# MAX17320.net
KiCad netlist of a schematic drawn in Altium Designer
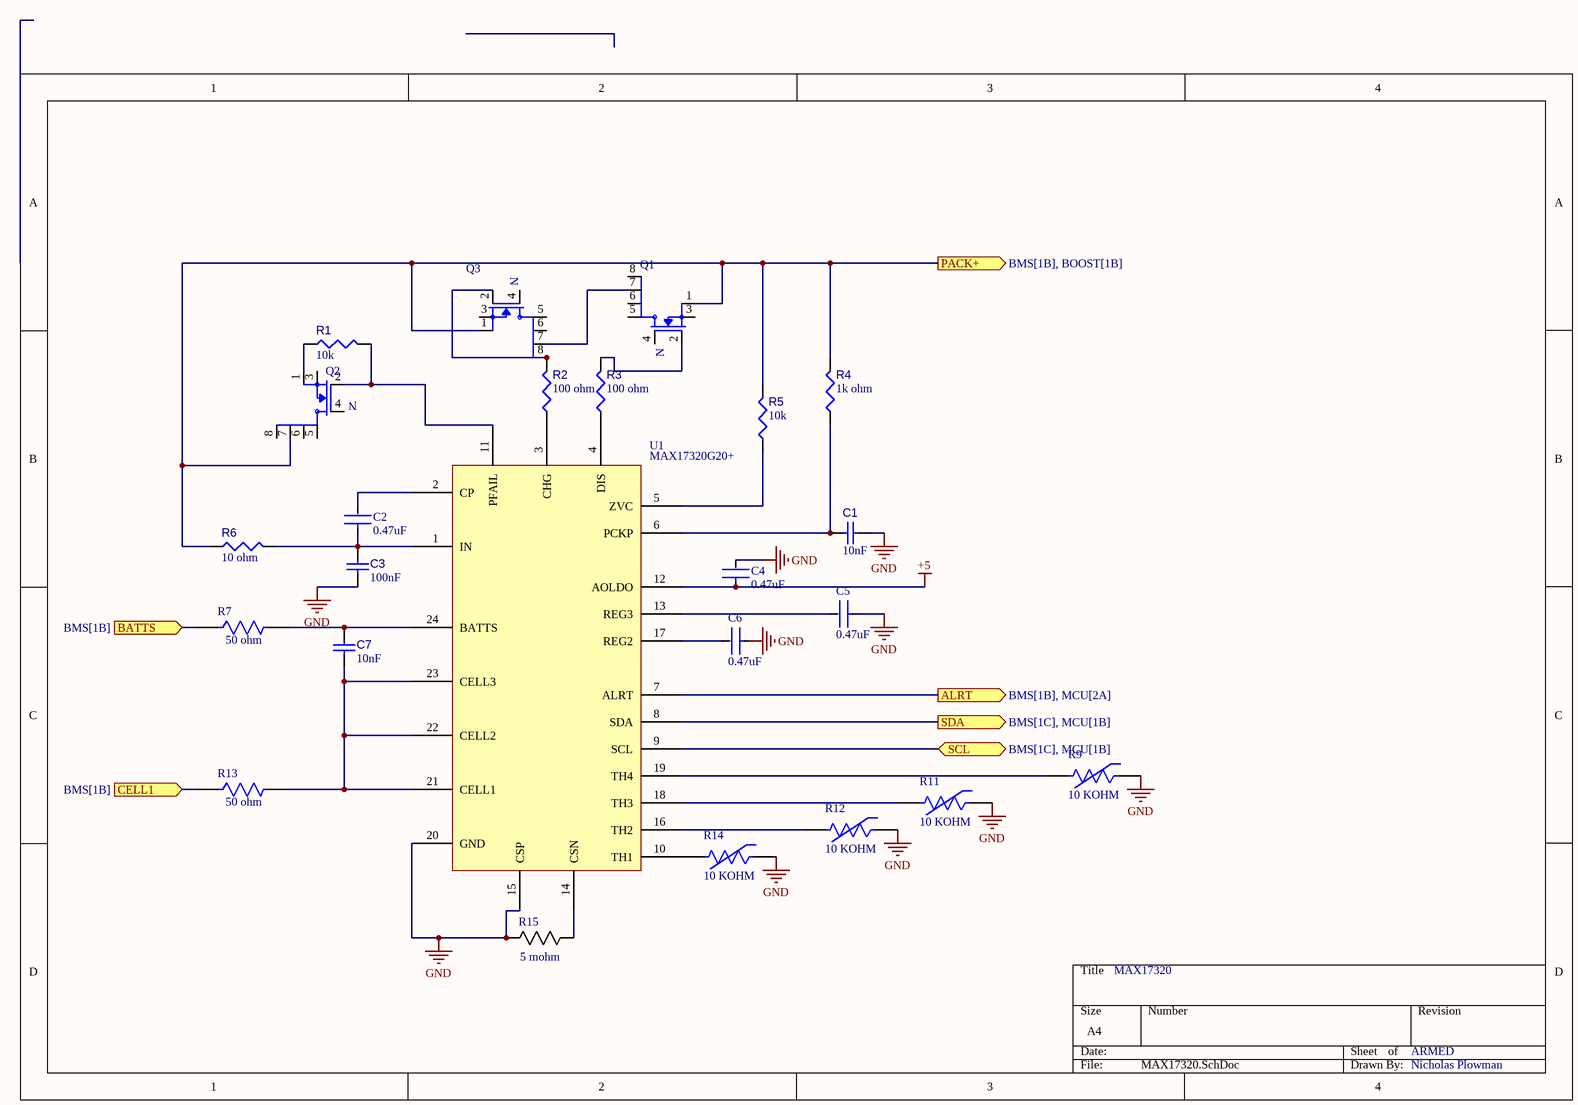
[diagram p0: MAX17320.SchDoc]

(export (version "E")
  (design (tool "Eeschema 10.0.6"))
  (components
    (comp (ref "C1")
      (value "10nF")
      (footprint "CAPC0402(1005)60_L")
      (description "Chip Capacitor, 10nF +/-20%, 50V, 0402, Thickness 0.6 mm")
      (fields (field (name "TOLERANCE") "5%") (field (name "Comment") "Capacitor 10nF +/-20% 50V 0402"))
      (libsource (lib "Americas- Augmented Reality for Medicine- University of Calgary") (part "CAP-NP-2"))
    )
    (comp (ref "C2")
      (value "0.47uF")
      (footprint "FP-GRM15-0_1-MFG")
      (description "Multilayer Ceramic Capacitor, 0.47 uF, 10 V, ± 10%, X5R, 0402 [1005 Metric]")
      (fields (field (name "Comment") "GRM155R61A474KE15D"))
      (libsource (lib "Americas- Augmented Reality for Medicine- University of Calgary") (part "11868f565c42a9108669ba33697ecf6"))
    )
    (comp (ref "C3")
      (value "100nF")
      (footprint "CAPC1005X56X25LL10T15")
      (description "Chip Capacitor, 0.1 uF, +/- 5%, 16 V, 0402 (1005 Metric)")
      (fields (field (name "TOLERANCE") "5%") (field (name "Comment") "Capacitor 0.1 uF +/- 5% 16 V 0402"))
      (libsource (lib "Americas- Augmented Reality for Medicine- University of Calgary") (part "CAP-NP-2"))
    )
    (comp (ref "C4")
      (value "0.47uF")
      (footprint "FP-GRM15-0_1-MFG")
      (description "Multilayer Ceramic Capacitor, 0.47 uF, 10 V, ± 10%, X5R, 0402 [1005 Metric]")
      (fields (field (name "Comment") "GRM155R61A474KE15D"))
      (libsource (lib "Americas- Augmented Reality for Medicine- University of Calgary") (part "11868f565c42a9108669ba33697ecf6"))
    )
    (comp (ref "C5")
      (value "0.47uF")
      (footprint "FP-GRM15-0_1-MFG")
      (description "Multilayer Ceramic Capacitor, 0.47 uF, 10 V, ± 10%, X5R, 0402 [1005 Metric]")
      (fields (field (name "Comment") "GRM155R61A474KE15D"))
      (libsource (lib "Americas- Augmented Reality for Medicine- University of Calgary") (part "11868f565c42a9108669ba33697ecf6"))
    )
    (comp (ref "C6")
      (value "0.47uF")
      (footprint "FP-GRM15-0_1-MFG")
      (description "Multilayer Ceramic Capacitor, 0.47 uF, 10 V, ± 10%, X5R, 0402 [1005 Metric]")
      (fields (field (name "Comment") "GRM155R61A474KE15D"))
      (libsource (lib "Americas- Augmented Reality for Medicine- University of Calgary") (part "11868f565c42a9108669ba33697ecf6"))
    )
    (comp (ref "C7")
      (value "10nF")
      (footprint "CAPC0402(1005)60_L")
      (description "Chip Capacitor, 10nF +/-20%, 50V, 0402, Thickness 0.6 mm")
      (fields (field (name "TOLERANCE") "5%") (field (name "Comment") "Capacitor 10nF +/-20% 50V 0402"))
      (libsource (lib "Americas- Augmented Reality for Medicine- University of Calgary") (part "CAP-NP-2"))
    )
    (comp (ref "Q1")
      (value "DN2625DK6-G-ND")
      (footprint "DN2625DK6-G-ND-Footprint-1")
      (description "MOSFET 2N-CH 250V 1.1A 8DFN")
      (libsource (lib "Americas- Augmented Reality for Medicine- University of Calgary") (part "DN2625DK6-G-ND-Symbol-1"))
    )
    (comp (ref "Q2")
      (value "DN2625DK6-G-ND")
      (footprint "DN2625DK6-G-ND-Footprint-1")
      (description "MOSFET 2N-CH 250V 1.1A 8DFN")
      (libsource (lib "Americas- Augmented Reality for Medicine- University of Calgary") (part "DN2625DK6-G-ND-Symbol-1"))
    )
    (comp (ref "Q3")
      (value "DN2625DK6-G-ND")
      (footprint "DN2625DK6-G-ND-Footprint-1")
      (description "MOSFET 2N-CH 250V 1.1A 8DFN")
      (libsource (lib "Americas- Augmented Reality for Medicine- University of Calgary") (part "DN2625DK6-G-ND-Symbol-1"))
    )
    (comp (ref "R1")
      (value "10k")
      (footprint "RESC1005X40X25ML05T05")
      (description "Chip Resistor, 10 KOhm, +/- 1%, 0.1 W, -55 to 155 degC, 0402 (1005 Metric)")
      (fields (field (name "TOLERANCE") "1%") (field (name "POWER") "100mW"))
      (libsource (lib "Americas- Augmented Reality for Medicine- University of Calgary") (part "RES-2"))
    )
    (comp (ref "R2")
      (value "100 ohm")
      (footprint "RESC0402(1005)_L")
      (description "100R 0.063W 1% 0402 (1005 Metric)  SMD")
      (fields (field (name "TOLERANCE") "1%") (field (name "POWER") "63mW"))
      (libsource (lib "Americas- Augmented Reality for Medicine- University of Calgary") (part "100R2F"))
    )
    (comp (ref "R3")
      (value "100 ohm")
      (footprint "RESC0402(1005)_L")
      (description "100R 0.063W 1% 0402 (1005 Metric)  SMD")
      (fields (field (name "TOLERANCE") "1%") (field (name "POWER") "63mW"))
      (libsource (lib "Americas- Augmented Reality for Medicine- University of Calgary") (part "100R2F"))
    )
    (comp (ref "R4")
      (value "1k ohm")
      (footprint "RESC0402(1005)_L")
      (description "1K 0.063W 5% 0402 (1005 Metric)  SMD")
      (fields (field (name "POWER") "63mW") (field (name "TOLERANCE") "5%"))
      (libsource (lib "Americas- Augmented Reality for Medicine- University of Calgary") (part "1KR2J"))
    )
    (comp (ref "R5")
      (value "10k")
      (footprint "RESC1005X40X25ML05T05")
      (description "Chip Resistor, 10 KOhm, +/- 1%, 0.1 W, -55 to 155 degC, 0402 (1005 Metric)")
      (fields (field (name "TOLERANCE") "1%") (field (name "POWER") "100mW"))
      (libsource (lib "Americas- Augmented Reality for Medicine- University of Calgary") (part "RES-2"))
    )
    (comp (ref "R6")
      (value "10 ohm")
      (footprint "RESC0402(1005)_L")
      (description "10R 0.063W 1% 0402 (1005 Metric)  SMD")
      (fields (field (name "TOLERANCE") "1%") (field (name "POWER") "63mW"))
      (libsource (lib "Americas- Augmented Reality for Medicine- University of Calgary") (part "10R2F"))
    )
    (comp (ref "R7")
      (value "50 ohm")
      (footprint "FP-CRCW0603-e3-IPC_A")
      (description "SMD Chip Resistor, 50 Ohm, ± 1%, 100 mW, 0603 [1608 Metric], Thick Film, General Purpose")
      (fields (field (name "Comment") "CRCW060350R0FKEA"))
      (libsource (lib "Americas- Augmented Reality for Medicine- University of Calgary") (part "1029c3af85768c4190bb7ad29bc67b5"))
    )
    (comp (ref "R9")
      (value "10 KOHM")
      (footprint "FP-NCP15-NCU15-0_05-MFG")
      (description "Ntc Thermistor, Aec-Q200, 10Kohm, 0402 Rohs Compliant: Yes")
      (fields (field (name "TOLERANCE") "1%"))
      (libsource (lib "Americas- Augmented Reality for Medicine- University of Calgary") (part "3b148a6ebabc5fb4d708a66c052d352"))
    )
    (comp (ref "R11")
      (value "10 KOHM")
      (footprint "FP-NCP15-NCU15-0_05-MFG")
      (description "Ntc Thermistor, Aec-Q200, 10Kohm, 0402 Rohs Compliant: Yes")
      (fields (field (name "TOLERANCE") "1%"))
      (libsource (lib "Americas- Augmented Reality for Medicine- University of Calgary") (part "3b148a6ebabc5fb4d708a66c052d352"))
    )
    (comp (ref "R12")
      (value "10 KOHM")
      (footprint "FP-NCP15-NCU15-0_05-MFG")
      (description "Ntc Thermistor, Aec-Q200, 10Kohm, 0402 Rohs Compliant: Yes")
      (fields (field (name "TOLERANCE") "1%"))
      (libsource (lib "Americas- Augmented Reality for Medicine- University of Calgary") (part "3b148a6ebabc5fb4d708a66c052d352"))
    )
    (comp (ref "R13")
      (value "50 ohm")
      (footprint "FP-CRCW0603-e3-IPC_A")
      (description "SMD Chip Resistor, 50 Ohm, ± 1%, 100 mW, 0603 [1608 Metric], Thick Film, General Purpose")
      (fields (field (name "Comment") "CRCW060350R0FKEA"))
      (libsource (lib "Americas- Augmented Reality for Medicine- University of Calgary") (part "1029c3af85768c4190bb7ad29bc67b5"))
    )
    (comp (ref "R14")
      (value "10 KOHM")
      (footprint "FP-NCP15-NCU15-0_05-MFG")
      (description "Ntc Thermistor, Aec-Q200, 10Kohm, 0402 Rohs Compliant: Yes")
      (fields (field (name "TOLERANCE") "1%"))
      (libsource (lib "Americas- Augmented Reality for Medicine- University of Calgary") (part "3b148a6ebabc5fb4d708a66c052d352"))
    )
    (comp (ref "R15")
      (value "PA2512FKF7W0R005E")
      (footprint "PA2512FKF7W0R005E-Footprint-1")
      (description "Res Thin Film 2512 5m Ohm 1% 2W ±100ppm/°C Molded SMD Embossed T/R")
      (fields (field (name "PARAMETER 1") "5 mohm"))
      (libsource (lib "Americas- Augmented Reality for Medicine- University of Calgary") (part "PA2512FKF7W0R005E-Symbol-1"))
    )
    (comp (ref "U1")
      (value "MAX17320G20+")
      (footprint "MAX17320G12+-Footprint-1")
      (description "Fuel Gauge 2S-4S ModelGauge m5 EZ with Protector I2C 4.2V to 18V 24-Pin TQFN")
      (libsource (lib "Americas- Augmented Reality for Medicine- University of Calgary") (part "MAX17320G12+-Symbol-1"))
    )
  )
  (nets
    (net (code "1") (name "+5") (class "Default")
      (node (ref "C4") (pin "1") (pinfunction "1_1") (pintype "passive"))
      (node (ref "U1") (pin "12") (pinfunction "AOLDO_12") (pintype "passive"))
    )
    (net (code "2") (name "/ALRT") (class "Default")
      (node (ref "U1") (pin "7") (pinfunction "ALRT_7") (pintype "passive"))
    )
    (net (code "3") (name "/BATTS") (class "Default")
      (node (ref "R7") (pin "1") (pinfunction "1_1") (pintype "passive"))
    )
    (net (code "4") (name "/CELL1") (class "Default")
      (node (ref "R13") (pin "1") (pinfunction "1_1") (pintype "passive"))
    )
    (net (code "5") (name "/PACK+") (class "Default")
      (node (ref "Q1") (pin "1") (pinfunction "S1_1") (pintype "passive"))
      (node (ref "Q2") (pin "7") (pinfunction "D1_1_7") (pintype "passive"))
      (node (ref "Q3") (pin "1") (pinfunction "S1_1") (pintype "passive"))
      (node (ref "R4") (pin "2") (pinfunction "2_2") (pintype "passive"))
      (node (ref "R5") (pin "2") (pinfunction "2_2") (pintype "passive"))
      (node (ref "R6") (pin "1") (pinfunction "1_1") (pintype "passive"))
    )
    (net (code "6") (name "/SCL") (class "Default")
      (node (ref "U1") (pin "9") (pinfunction "SCL_9") (pintype "passive"))
    )
    (net (code "7") (name "/SDA") (class "Default")
      (node (ref "U1") (pin "8") (pinfunction "SDA_8") (pintype "passive"))
    )
    (net (code "8") (name "GND") (class "Default")
      (node (ref "C1") (pin "1") (pinfunction "1_1") (pintype "passive"))
      (node (ref "C3") (pin "1") (pinfunction "1_1") (pintype "passive"))
      (node (ref "C4") (pin "2") (pinfunction "2_2") (pintype "passive"))
      (node (ref "C5") (pin "1") (pinfunction "1_1") (pintype "passive"))
      (node (ref "C6") (pin "1") (pinfunction "1_1") (pintype "passive"))
      (node (ref "R11") (pin "1") (pinfunction "1_1") (pintype "passive"))
      (node (ref "R12") (pin "1") (pinfunction "1_1") (pintype "passive"))
      (node (ref "R14") (pin "1") (pinfunction "1_1") (pintype "passive"))
      (node (ref "R15") (pin "1") (pinfunction "1_1") (pintype "passive"))
      (node (ref "R9") (pin "1") (pinfunction "1_1") (pintype "passive"))
      (node (ref "U1") (pin "15") (pinfunction "CSP_15") (pintype "passive"))
      (node (ref "U1") (pin "20") (pinfunction "GND_20") (pintype "passive"))
    )
    (net (code "9") (name "Net-(Q1-D1_1)") (class "Default")
      (node (ref "Q1") (pin "7") (pinfunction "D1_1_7") (pintype "passive"))
      (node (ref "Q3") (pin "7") (pinfunction "D1_1_7") (pintype "passive"))
    )
    (net (code "10") (name "Net-(Q1-G1)") (class "Default")
      (node (ref "Q1") (pin "2") (pinfunction "G1_2") (pintype "passive"))
      (node (ref "R3") (pin "2") (pinfunction "2_2") (pintype "passive"))
    )
    (net (code "11") (name "Net-(Q2-G1)") (class "Default")
      (node (ref "Q2") (pin "2") (pinfunction "G1_2") (pintype "passive"))
      (node (ref "R1") (pin "2") (pinfunction "2_2") (pintype "passive"))
      (node (ref "U1") (pin "11") (pinfunction "_PFAIL_11") (pintype "passive"))
    )
    (net (code "12") (name "Net-(Q2-S1)") (class "Default")
      (node (ref "Q2") (pin "1") (pinfunction "S1_1") (pintype "passive"))
      (node (ref "R1") (pin "1") (pinfunction "1_1") (pintype "passive"))
    )
    (net (code "13") (name "Net-(Q3-D1_2)") (class "Default")
      (node (ref "Q3") (pin "2") (pinfunction "G1_2") (pintype "passive"))
      (node (ref "Q3") (pin "8") (pinfunction "D1_2_8") (pintype "passive"))
      (node (ref "R2") (pin "2") (pinfunction "2_2") (pintype "passive"))
    )
    (net (code "14") (name "Net-(U1-BATTS)") (class "Default")
      (node (ref "C7") (pin "2") (pinfunction "2_2") (pintype "passive"))
      (node (ref "R7") (pin "2") (pinfunction "2_2") (pintype "passive"))
      (node (ref "U1") (pin "24") (pinfunction "BATTS_24") (pintype "passive"))
    )
    (net (code "15") (name "Net-(U1-CELL1)") (class "Default")
      (node (ref "C7") (pin "1") (pinfunction "1_1") (pintype "passive"))
      (node (ref "R13") (pin "2") (pinfunction "2_2") (pintype "passive"))
      (node (ref "U1") (pin "21") (pinfunction "CELL1_21") (pintype "passive"))
      (node (ref "U1") (pin "22") (pinfunction "CELL2_22") (pintype "passive"))
      (node (ref "U1") (pin "23") (pinfunction "CELL3_23") (pintype "passive"))
    )
    (net (code "16") (name "Net-(U1-CHG)") (class "Default")
      (node (ref "R2") (pin "1") (pinfunction "1_1") (pintype "passive"))
      (node (ref "U1") (pin "3") (pinfunction "CHG_3") (pintype "passive"))
    )
    (net (code "17") (name "Net-(U1-CP)") (class "Default")
      (node (ref "C2") (pin "2") (pinfunction "2_2") (pintype "passive"))
      (node (ref "U1") (pin "2") (pinfunction "CP_2") (pintype "passive"))
    )
    (net (code "18") (name "Net-(U1-CSN)") (class "Default")
      (node (ref "R15") (pin "2") (pinfunction "2_2") (pintype "passive"))
      (node (ref "U1") (pin "14") (pinfunction "CSN_14") (pintype "passive"))
    )
    (net (code "19") (name "Net-(U1-IN)") (class "Default")
      (node (ref "C2") (pin "1") (pinfunction "1_1") (pintype "passive"))
      (node (ref "C3") (pin "2") (pinfunction "2_2") (pintype "passive"))
      (node (ref "R6") (pin "2") (pinfunction "2_2") (pintype "passive"))
      (node (ref "U1") (pin "1") (pinfunction "IN_1") (pintype "passive"))
    )
    (net (code "20") (name "Net-(U1-PCKP)") (class "Default")
      (node (ref "C1") (pin "2") (pinfunction "2_2") (pintype "passive"))
      (node (ref "R4") (pin "1") (pinfunction "1_1") (pintype "passive"))
      (node (ref "U1") (pin "6") (pinfunction "PCKP_6") (pintype "passive"))
    )
    (net (code "21") (name "Net-(U1-REG2)") (class "Default")
      (node (ref "C6") (pin "2") (pinfunction "2_2") (pintype "passive"))
      (node (ref "U1") (pin "17") (pinfunction "REG2_17") (pintype "passive"))
    )
    (net (code "22") (name "Net-(U1-REG3)") (class "Default")
      (node (ref "C5") (pin "2") (pinfunction "2_2") (pintype "passive"))
      (node (ref "U1") (pin "13") (pinfunction "REG3_13") (pintype "passive"))
    )
    (net (code "23") (name "Net-(U1-TH1)") (class "Default")
      (node (ref "R14") (pin "2") (pinfunction "2_2") (pintype "passive"))
      (node (ref "U1") (pin "10") (pinfunction "TH1_10") (pintype "passive"))
    )
    (net (code "24") (name "Net-(U1-TH2)") (class "Default")
      (node (ref "R12") (pin "2") (pinfunction "2_2") (pintype "passive"))
      (node (ref "U1") (pin "16") (pinfunction "TH2_16") (pintype "passive"))
    )
    (net (code "25") (name "Net-(U1-TH3)") (class "Default")
      (node (ref "R11") (pin "2") (pinfunction "2_2") (pintype "passive"))
      (node (ref "U1") (pin "18") (pinfunction "TH3_18") (pintype "passive"))
    )
    (net (code "26") (name "Net-(U1-TH4)") (class "Default")
      (node (ref "R9") (pin "2") (pinfunction "2_2") (pintype "passive"))
      (node (ref "U1") (pin "19") (pinfunction "TH4_19") (pintype "passive"))
    )
    (net (code "27") (name "Net-(U1-ZVC)") (class "Default")
      (node (ref "R5") (pin "1") (pinfunction "1_1") (pintype "passive"))
      (node (ref "U1") (pin "5") (pinfunction "ZVC_5") (pintype "passive"))
    )
    (net (code "28") (name "Net-(U1-_DIS)") (class "Default")
      (node (ref "R3") (pin "1") (pinfunction "1_1") (pintype "passive"))
      (node (ref "U1") (pin "4") (pinfunction "_DIS_4") (pintype "passive"))
    )
    (net (code "29") (name "unconnected-(Q1-D1_2-Pad8)") (class "Default")
      (node (ref "Q1") (pin "8") (pinfunction "D1_2_8") (pintype "passive"))
    )
    (net (code "30") (name "unconnected-(Q1-D2_1-Pad5)") (class "Default")
      (node (ref "Q1") (pin "5") (pinfunction "D2_1_5") (pintype "passive"))
    )
    (net (code "31") (name "unconnected-(Q1-D2_2-Pad6)") (class "Default")
      (node (ref "Q1") (pin "6") (pinfunction "D2_2_6") (pintype "passive"))
    )
    (net (code "32") (name "unconnected-(Q1-G2-Pad4)") (class "Default")
      (node (ref "Q1") (pin "4") (pinfunction "G2_4") (pintype "passive"))
    )
    (net (code "33") (name "unconnected-(Q1-S2-Pad3)") (class "Default")
      (node (ref "Q1") (pin "3") (pinfunction "S2_3") (pintype "passive"))
    )
    (net (code "34") (name "unconnected-(Q2-D1_2-Pad8)") (class "Default")
      (node (ref "Q2") (pin "8") (pinfunction "D1_2_8") (pintype "passive"))
    )
    (net (code "35") (name "unconnected-(Q2-D2_1-Pad5)") (class "Default")
      (node (ref "Q2") (pin "5") (pinfunction "D2_1_5") (pintype "passive"))
    )
    (net (code "36") (name "unconnected-(Q2-D2_2-Pad6)") (class "Default")
      (node (ref "Q2") (pin "6") (pinfunction "D2_2_6") (pintype "passive"))
    )
    (net (code "37") (name "unconnected-(Q2-G2-Pad4)") (class "Default")
      (node (ref "Q2") (pin "4") (pinfunction "G2_4") (pintype "passive"))
    )
    (net (code "38") (name "unconnected-(Q2-S2-Pad3)") (class "Default")
      (node (ref "Q2") (pin "3") (pinfunction "S2_3") (pintype "passive"))
    )
    (net (code "39") (name "unconnected-(Q3-D2_1-Pad5)") (class "Default")
      (node (ref "Q3") (pin "5") (pinfunction "D2_1_5") (pintype "passive"))
    )
    (net (code "40") (name "unconnected-(Q3-D2_2-Pad6)") (class "Default")
      (node (ref "Q3") (pin "6") (pinfunction "D2_2_6") (pintype "passive"))
    )
    (net (code "41") (name "unconnected-(Q3-G2-Pad4)") (class "Default")
      (node (ref "Q3") (pin "4") (pinfunction "G2_4") (pintype "passive"))
    )
    (net (code "42") (name "unconnected-(Q3-S2-Pad3)") (class "Default")
      (node (ref "Q3") (pin "3") (pinfunction "S2_3") (pintype "passive"))
    )
  )
)
